# 5_shkb_power_supply.net
KiCad netlist of a schematic drawn in Altium Designer
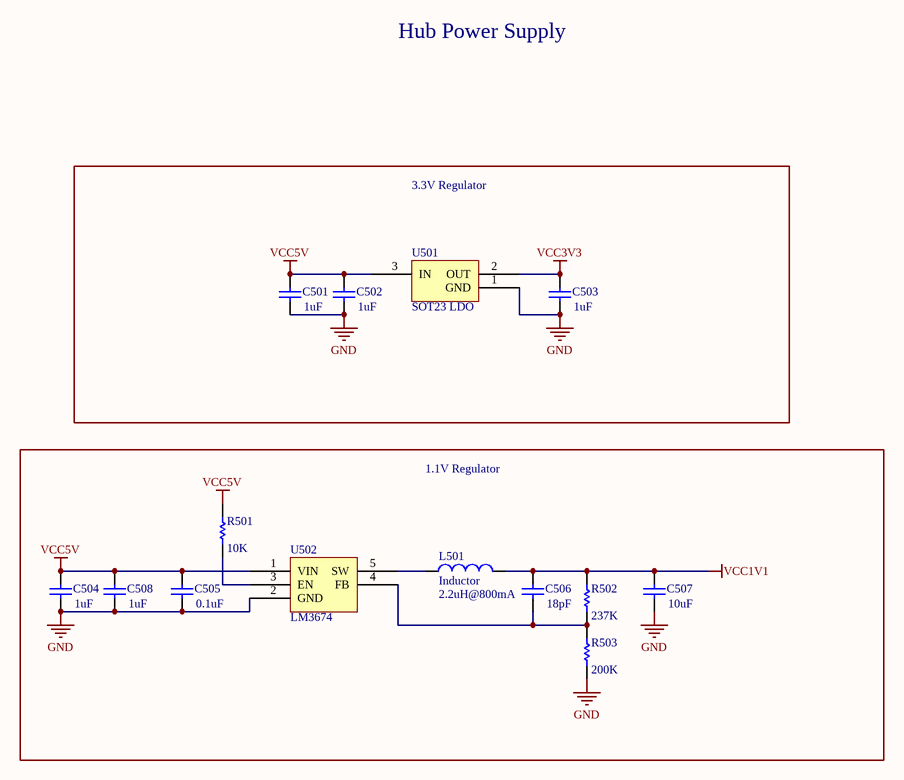
[diagram p0: 5_shkb_power_supply.SchDoc]

(export (version "E")
  (design (tool "Eeschema 10.0.6"))
  (components
    (comp (ref "C501")
      (value "1uF")
      (footprint "C0603[1608]")
      (description "Capacitor")
      (fields (field (name "MFG") "KEMET") (field (name "LCSC PART #") "C15849"))
      (libsource (lib "Miscellaneous Devices") (part "Cap"))
    )
    (comp (ref "C502")
      (value "1uF")
      (footprint "C0603[1608]")
      (description "Capacitor")
      (fields (field (name "MFG") "KEMET") (field (name "LCSC PART #") "C15849"))
      (libsource (lib "Miscellaneous Devices") (part "Cap"))
    )
    (comp (ref "C503")
      (value "1uF")
      (footprint "C0603[1608]")
      (description "Capacitor")
      (fields (field (name "MFG") "KEMET") (field (name "LCSC PART #") "C15849"))
      (libsource (lib "Miscellaneous Devices") (part "Cap"))
    )
    (comp (ref "C504")
      (value "1uF")
      (footprint "C0603[1608]")
      (description "Capacitor")
      (fields (field (name "MFG") "KEMET") (field (name "LCSC PART #") "C15849"))
      (libsource (lib "Miscellaneous Devices") (part "Cap"))
    )
    (comp (ref "C505")
      (value "0.1uF")
      (footprint "C0603[1608]")
      (description "Capacitor")
      (fields (field (name "MFG") "KEMET") (field (name "LCSC PART #") "C14663"))
      (libsource (lib "Miscellaneous Devices") (part "Cap"))
    )
    (comp (ref "C506")
      (value "18pF")
      (footprint "C0603[1608]")
      (description "Capacitor")
      (fields (field (name "MFG") "KEMET") (field (name "LCSC PART #") "C1647"))
      (libsource (lib "Miscellaneous Devices") (part "Cap"))
    )
    (comp (ref "C507")
      (value "10uF")
      (footprint "C1206[3216]")
      (description "Capacitor")
      (fields (field (name "MFG") "KEMET") (field (name "LCSC PART #") "C13585"))
      (libsource (lib "Miscellaneous Devices") (part "Cap"))
    )
    (comp (ref "C508")
      (value "1uF")
      (footprint "C0603[1608]")
      (description "Capacitor")
      (fields (field (name "MFG") "KEMET") (field (name "LCSC PART #") "C15849"))
      (libsource (lib "Miscellaneous Devices") (part "Cap"))
    )
    (comp (ref "L501")
      (value "Inductor")
      (footprint "C0805")
      (fields
        (field (name "ALTIUM_VALUE") "2.2uH@800mA")
        (field (name "MFG") "TDK")
        (field (name "LCSC PART #") "C107322")
        (field (name "MRF.PART") "MLP2012S2R2MT0S1")
      )
      (libsource (lib "Miscellaneous Devices") (part "Inductor"))
    )
    (comp (ref "R501")
      (value "10K")
      (footprint "R0603[1608]")
      (description "Resistor")
      (fields (field (name "MFG") "Vishay Dale") (field (name "LCSC PART #") "C25804"))
      (libsource (lib "Miscellaneous Devices") (part "Res1"))
    )
    (comp (ref "R502")
      (value "237K")
      (footprint "R0603[1608]")
      (description "Resistor")
      (fields (field (name "MFG") "Vishay Dale") (field (name "LCSC PART #") "C22914"))
      (libsource (lib "Miscellaneous Devices") (part "Res1"))
    )
    (comp (ref "R503")
      (value "200K")
      (footprint "R0603[1608]")
      (description "Resistor")
      (fields (field (name "MFG") "Vishay Dale") (field (name "LCSC PART #") "C25811"))
      (libsource (lib "Miscellaneous Devices") (part "Res1"))
    )
    (comp (ref "U501")
      (value "SOT23 LDO")
      (footprint "SOT-23-3")
      (fields
        (field (name "LCSC PART #") "C5446")
        (field (name "MRF.PART") "XC6206P332MR")
        (field (name "MFG") "Texas Instruments")
      )
      (libsource (lib "Keebs") (part "SOT23 LDO"))
    )
    (comp (ref "U502")
      (value "LM3674")
      (footprint "SOT-23-5")
      (fields
        (field (name "MFG") "Texas Instruments")
        (field (name "LCSC PART #") "C52027")
        (field (name "MRF.PART") "LM3674MF-ADJ/NOPB")
      )
      (libsource (lib "lib") (part "LM3674"))
    )
  )
  (nets
    (net (code "1") (name "GND") (class "Default")
      (node (ref "C501") (pin "1") (pinfunction "1_1") (pintype "passive"))
      (node (ref "C502") (pin "1") (pinfunction "1_1") (pintype "passive"))
      (node (ref "C503") (pin "1") (pinfunction "1_1") (pintype "passive"))
      (node (ref "C504") (pin "1") (pinfunction "1_1") (pintype "passive"))
      (node (ref "C505") (pin "1") (pinfunction "1_1") (pintype "passive"))
      (node (ref "C507") (pin "1") (pinfunction "1_1") (pintype "passive"))
      (node (ref "C508") (pin "1") (pinfunction "1_1") (pintype "passive"))
      (node (ref "R503") (pin "2") (pinfunction "2_2") (pintype "passive"))
      (node (ref "U501") (pin "1") (pinfunction "GND_1") (pintype "passive"))
      (node (ref "U502") (pin "2") (pinfunction "GND_2") (pintype "passive"))
    )
    (net (code "2") (name "Net-(U502-EN)") (class "Default")
      (node (ref "R501") (pin "2") (pinfunction "2_2") (pintype "passive"))
      (node (ref "U502") (pin "3") (pinfunction "EN_3") (pintype "passive"))
    )
    (net (code "3") (name "Net-(U502-FB)") (class "Default")
      (node (ref "C506") (pin "1") (pinfunction "1_1") (pintype "passive"))
      (node (ref "R502") (pin "2") (pinfunction "2_2") (pintype "passive"))
      (node (ref "R503") (pin "1") (pinfunction "1_1") (pintype "passive"))
      (node (ref "U502") (pin "4") (pinfunction "FB_4") (pintype "passive"))
    )
    (net (code "4") (name "Net-(U502-SW)") (class "Default")
      (node (ref "L501") (pin "1") (pinfunction "1_1") (pintype "passive"))
      (node (ref "U502") (pin "5") (pinfunction "SW_5") (pintype "passive"))
    )
    (net (code "5") (name "VCC1V1") (class "Default")
      (node (ref "C506") (pin "2") (pinfunction "2_2") (pintype "passive"))
      (node (ref "C507") (pin "2") (pinfunction "2_2") (pintype "passive"))
      (node (ref "L501") (pin "2") (pinfunction "2_2") (pintype "passive"))
      (node (ref "R502") (pin "1") (pinfunction "1_1") (pintype "passive"))
    )
    (net (code "6") (name "VCC3V3") (class "Default")
      (node (ref "C503") (pin "2") (pinfunction "2_2") (pintype "passive"))
      (node (ref "U501") (pin "2") (pinfunction "OUT_2") (pintype "passive"))
    )
    (net (code "7") (name "VCC5V") (class "Default")
      (node (ref "C501") (pin "2") (pinfunction "2_2") (pintype "passive"))
      (node (ref "C502") (pin "2") (pinfunction "2_2") (pintype "passive"))
      (node (ref "C504") (pin "2") (pinfunction "2_2") (pintype "passive"))
      (node (ref "C505") (pin "2") (pinfunction "2_2") (pintype "passive"))
      (node (ref "C508") (pin "2") (pinfunction "2_2") (pintype "passive"))
      (node (ref "R501") (pin "1") (pinfunction "1_1") (pintype "passive"))
      (node (ref "U501") (pin "3") (pinfunction "IN_3") (pintype "passive"))
      (node (ref "U502") (pin "1") (pinfunction "VIN_1") (pintype "passive"))
    )
  )
)
